# AFE.net
KiCad netlist of a schematic drawn in Altium Designer
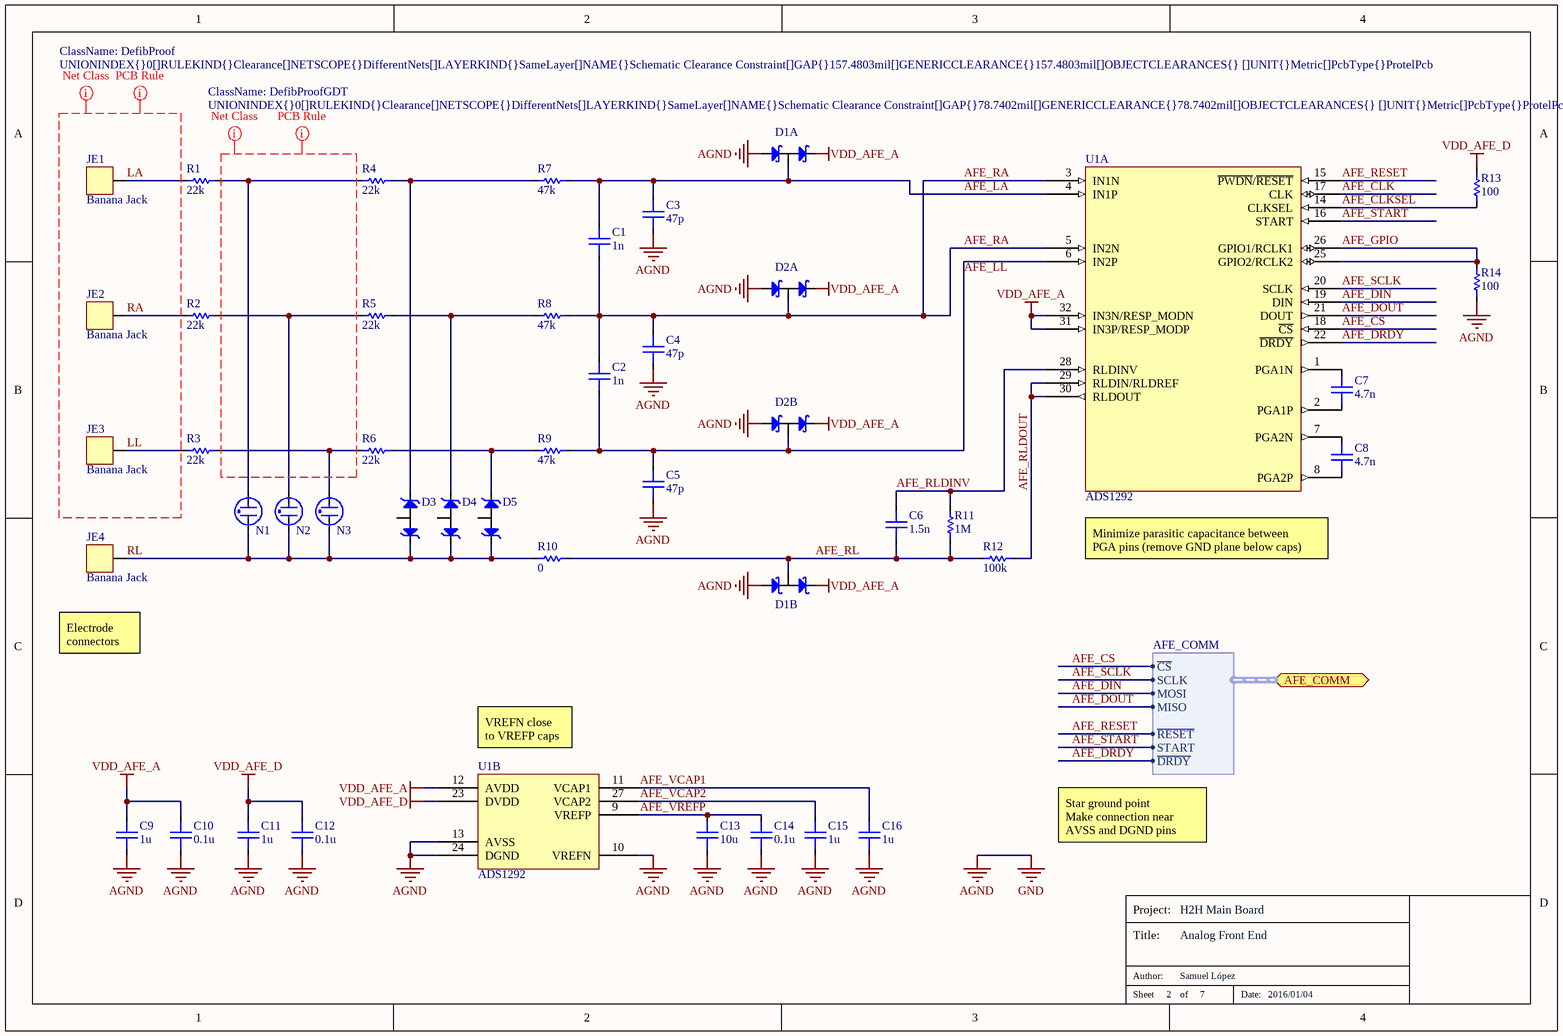
[diagram p0: AFE.SchDoc]

(export (version "E")
  (design (tool "Eeschema 10.0.6"))
  (components
    (comp (ref "C1")
      (value "1n")
      (footprint "C0603")
      (description "Capacitor")
      (libsource (lib "Misc") (part "Capacitor"))
    )
    (comp (ref "C2")
      (value "1n")
      (footprint "C0603")
      (description "Capacitor")
      (libsource (lib "Misc") (part "Capacitor"))
    )
    (comp (ref "C3")
      (value "47p")
      (footprint "C0603")
      (description "Capacitor")
      (libsource (lib "Misc") (part "Capacitor"))
    )
    (comp (ref "C4")
      (value "47p")
      (footprint "C0603")
      (description "Capacitor")
      (libsource (lib "Misc") (part "Capacitor"))
    )
    (comp (ref "C5")
      (value "47p")
      (footprint "C0603")
      (description "Capacitor")
      (libsource (lib "Misc") (part "Capacitor"))
    )
    (comp (ref "C6")
      (value "1.5n")
      (footprint "C0603")
      (description "Capacitor")
      (libsource (lib "Misc") (part "Capacitor"))
    )
    (comp (ref "C7")
      (value "4.7n")
      (footprint "C0603")
      (description "Capacitor")
      (libsource (lib "Misc") (part "Capacitor"))
    )
    (comp (ref "C8")
      (value "4.7n")
      (footprint "C0603")
      (description "Capacitor")
      (libsource (lib "Misc") (part "Capacitor"))
    )
    (comp (ref "C9")
      (value "1u")
      (footprint "C0603")
      (description "Capacitor")
      (libsource (lib "Misc") (part "Capacitor"))
    )
    (comp (ref "C10")
      (value "0.1u")
      (footprint "C0603")
      (description "Capacitor")
      (libsource (lib "Misc") (part "Capacitor"))
    )
    (comp (ref "C11")
      (value "1u")
      (footprint "C0603")
      (description "Capacitor")
      (libsource (lib "Misc") (part "Capacitor"))
    )
    (comp (ref "C12")
      (value "0.1u")
      (footprint "C0603")
      (description "Capacitor")
      (libsource (lib "Misc") (part "Capacitor"))
    )
    (comp (ref "C13")
      (value "10u")
      (footprint "C0603")
      (description "Capacitor")
      (libsource (lib "Misc") (part "Capacitor"))
    )
    (comp (ref "C14")
      (value "0.1u")
      (footprint "C0603")
      (description "Capacitor")
      (libsource (lib "Misc") (part "Capacitor"))
    )
    (comp (ref "C15")
      (value "1u")
      (footprint "C0603")
      (description "Capacitor")
      (libsource (lib "Misc") (part "Capacitor"))
    )
    (comp (ref "C16")
      (value "1u")
      (footprint "C0603")
      (description "Capacitor")
      (libsource (lib "Misc") (part "Capacitor"))
    )
    (comp (ref "D1")
      (value "BAS70DW-04")
      (footprint "BAS70DW-04")
      (description "TVS - Dual Schottky Rail-to-rail Protection")
      (libsource (lib "") (part "BAS70DW-04_1"))
    )
    (comp (ref "D2")
      (value "BAS70DW-04")
      (footprint "BAS70DW-04")
      (description "TVS - Dual Schottky Rail-to-rail Protection")
      (libsource (lib "H2H") (part "BAS70DW-04"))
    )
    (comp (ref "D3")
      (value "PESD5V0X1")
      (footprint "PESD5V0X1BT")
      (description "TVS - Bidirectional Zener Diode")
      (libsource (lib "H2H") (part "PESD5V0X1"))
    )
    (comp (ref "D4")
      (value "PESD5V0X1")
      (footprint "PESD5V0X1BT")
      (description "TVS - Bidirectional Zener Diode")
      (libsource (lib "H2H") (part "PESD5V0X1"))
    )
    (comp (ref "D5")
      (value "PESD5V0X1")
      (footprint "PESD5V0X1BT")
      (description "TVS - Bidirectional Zener Diode")
      (libsource (lib "H2H") (part "PESD5V0X1"))
    )
    (comp (ref "JE1")
      (value "Banana Jack")
      (footprint "CT3151-6")
      (description "Conn - 4mm Banana Female Jack, PCB mount, Right Angle")
      (libsource (lib "Conn") (part "CT3151SP-6"))
    )
    (comp (ref "JE2")
      (value "Banana Jack")
      (footprint "CT3151-6")
      (description "Conn - 4mm Banana Female Jack, PCB mount, Right Angle")
      (libsource (lib "Conn") (part "CT3151SP-6"))
    )
    (comp (ref "JE3")
      (value "Banana Jack")
      (footprint "CT3151-6")
      (description "Conn - 4mm Banana Female Jack, PCB mount, Right Angle")
      (libsource (lib "Conn") (part "CT3151SP-6"))
    )
    (comp (ref "JE4")
      (value "Banana Jack")
      (footprint "CT3151-6")
      (description "Conn - 4mm Banana Female Jack, PCB mount, Right Angle")
      (libsource (lib "Conn") (part "CT3151SP-6"))
    )
    (comp (ref "N1")
      (value "GDT")
      (footprint "2051-09-SM")
      (description "TVS - Gas Discharge Tube")
      (libsource (lib "H2H") (part "2051-09-SM"))
    )
    (comp (ref "N2")
      (value "GDT")
      (footprint "2051-09-SM")
      (description "TVS - Gas Discharge Tube")
      (libsource (lib "H2H") (part "2051-09-SM"))
    )
    (comp (ref "N3")
      (value "GDT")
      (footprint "2051-09-SM")
      (description "TVS - Gas Discharge Tube")
      (libsource (lib "H2H") (part "2051-09-SM"))
    )
    (comp (ref "R1")
      (value "22k")
      (footprint "R2512")
      (description "Resistor")
      (fields (field (name "POWER") "1W"))
      (libsource (lib "Misc") (part "Resistor"))
    )
    (comp (ref "R2")
      (value "22k")
      (footprint "R2512")
      (description "Resistor")
      (fields (field (name "POWER") "1W"))
      (libsource (lib "Misc") (part "Resistor"))
    )
    (comp (ref "R3")
      (value "22k")
      (footprint "R2512")
      (description "Resistor")
      (fields (field (name "POWER") "1W"))
      (libsource (lib "Misc") (part "Resistor"))
    )
    (comp (ref "R4")
      (value "22k")
      (footprint "R2512")
      (description "Resistor")
      (fields (field (name "POWER") "1W"))
      (libsource (lib "Misc") (part "Resistor"))
    )
    (comp (ref "R5")
      (value "22k")
      (footprint "R2512")
      (description "Resistor")
      (fields (field (name "POWER") "1W"))
      (libsource (lib "Misc") (part "Resistor"))
    )
    (comp (ref "R6")
      (value "22k")
      (footprint "R2512")
      (description "Resistor")
      (fields (field (name "POWER") "1W"))
      (libsource (lib "Misc") (part "Resistor"))
    )
    (comp (ref "R7")
      (value "47k")
      (footprint "R0603")
      (description "Resistor")
      (libsource (lib "Misc") (part "Resistor"))
    )
    (comp (ref "R8")
      (value "47k")
      (footprint "R0603")
      (description "Resistor")
      (libsource (lib "Misc") (part "Resistor"))
    )
    (comp (ref "R9")
      (value "47k")
      (footprint "R0603")
      (description "Resistor")
      (libsource (lib "Misc") (part "Resistor"))
    )
    (comp (ref "R10")
      (value "0")
      (footprint "R0603")
      (description "Resistor")
      (libsource (lib "Misc") (part "Resistor"))
    )
    (comp (ref "R11")
      (value "1M")
      (footprint "R0603")
      (description "Resistor")
      (libsource (lib "Misc") (part "Resistor"))
    )
    (comp (ref "R12")
      (value "100k")
      (footprint "R0603")
      (description "Resistor")
      (libsource (lib "Misc") (part "Resistor"))
    )
    (comp (ref "R13")
      (value "100")
      (footprint "R0603")
      (description "Resistor")
      (libsource (lib "Misc") (part "Resistor"))
    )
    (comp (ref "R14")
      (value "100")
      (footprint "R0603")
      (description "Resistor")
      (libsource (lib "Misc") (part "Resistor"))
    )
    (comp (ref "U1")
      (value "ADS1292")
      (footprint "ADS129x")
      (description "IC - Analog Front End - Medical")
      (libsource (lib "H2H") (part "ADS1292"))
    )
  )
  (nets
    (net (code "2") (name "/AFE_CLK") (class "Default")
      (node (ref "U1") (pin "17") (pinfunction "CLK_17") (pintype "bidirectional"))
    )
    (net (code "3") (name "/AFE_CLKSEL") (class "Default")
      (node (ref "R13") (pin "2") (pinfunction "2_2") (pintype "passive"))
      (node (ref "U1") (pin "14") (pinfunction "CLKSEL_14") (pintype "input"))
    )
    (net (code "4") (name "/AFE_CS") (class "Default")
      (node (ref "U1") (pin "18") (pinfunction "~{CS}_18") (pintype "input"))
    )
    (net (code "5") (name "/AFE_DIN") (class "Default")
      (node (ref "U1") (pin "19") (pinfunction "DIN_19") (pintype "input"))
    )
    (net (code "6") (name "/AFE_DOUT") (class "Default")
      (node (ref "U1") (pin "21") (pinfunction "DOUT_21") (pintype "output"))
    )
    (net (code "7") (name "/AFE_DRDY") (class "Default")
      (node (ref "U1") (pin "22") (pinfunction "~{DRDY}_22") (pintype "output"))
    )
    (net (code "8") (name "/AFE_GPIO") (class "Default")
      (node (ref "R14") (pin "1") (pinfunction "1_1") (pintype "passive"))
      (node (ref "U1") (pin "25") (pinfunction "GPIO2/RCLK2_25") (pintype "bidirectional"))
      (node (ref "U1") (pin "26") (pinfunction "GPIO1/RCLK1_26") (pintype "bidirectional"))
    )
    (net (code "9") (name "/AFE_LA") (class "Default")
      (node (ref "C1") (pin "2") (pinfunction "2_2") (pintype "passive"))
      (node (ref "C3") (pin "2") (pinfunction "2_2") (pintype "passive"))
      (node (ref "D1") (pin "6") (pinfunction "AK1_6") (pintype "passive"))
      (node (ref "R7") (pin "2") (pinfunction "2_2") (pintype "passive"))
      (node (ref "U1") (pin "4") (pinfunction "IN1P_4") (pintype "input"))
    )
    (net (code "10") (name "/AFE_LL") (class "Default")
      (node (ref "C2") (pin "1") (pinfunction "1_1") (pintype "passive"))
      (node (ref "C5") (pin "2") (pinfunction "2_2") (pintype "passive"))
      (node (ref "D2") (pin "3") (pinfunction "AK2_3") (pintype "passive"))
      (node (ref "R9") (pin "2") (pinfunction "2_2") (pintype "passive"))
      (node (ref "U1") (pin "6") (pinfunction "IN2P_6") (pintype "input"))
    )
    (net (code "11") (name "/AFE_RA") (class "Default")
      (node (ref "C1") (pin "1") (pinfunction "1_1") (pintype "passive"))
      (node (ref "C2") (pin "2") (pinfunction "2_2") (pintype "passive"))
      (node (ref "C4") (pin "2") (pinfunction "2_2") (pintype "passive"))
      (node (ref "D2") (pin "6") (pinfunction "AK1_6") (pintype "passive"))
      (node (ref "R8") (pin "2") (pinfunction "2_2") (pintype "passive"))
      (node (ref "U1") (pin "3") (pinfunction "IN1N_3") (pintype "input"))
      (node (ref "U1") (pin "5") (pinfunction "IN2N_5") (pintype "input"))
    )
    (net (code "12") (name "/AFE_RESET") (class "Default")
      (node (ref "U1") (pin "15") (pinfunction "~{PWDN}/~{RESET}_15") (pintype "input"))
    )
    (net (code "13") (name "/AFE_RL") (class "Default")
      (node (ref "C6") (pin "2") (pinfunction "2_2") (pintype "passive"))
      (node (ref "D1") (pin "3") (pinfunction "AK2_3") (pintype "passive"))
      (node (ref "R10") (pin "2") (pinfunction "2_2") (pintype "passive"))
      (node (ref "R11") (pin "2") (pinfunction "2_2") (pintype "passive"))
      (node (ref "R12") (pin "2") (pinfunction "2_2") (pintype "passive"))
    )
    (net (code "14") (name "/AFE_RLDINV") (class "Default")
      (node (ref "C6") (pin "1") (pinfunction "1_1") (pintype "passive"))
      (node (ref "R11") (pin "1") (pinfunction "1_1") (pintype "passive"))
      (node (ref "U1") (pin "28") (pinfunction "RLDINV_28") (pintype "input"))
    )
    (net (code "15") (name "/AFE_RLDOUT") (class "Default")
      (node (ref "R12") (pin "1") (pinfunction "1_1") (pintype "passive"))
      (node (ref "U1") (pin "29") (pinfunction "RLDIN/RLDREF_29") (pintype "input"))
      (node (ref "U1") (pin "30") (pinfunction "RLDOUT_30") (pintype "output"))
    )
    (net (code "16") (name "/AFE_SCLK") (class "Default")
      (node (ref "U1") (pin "20") (pinfunction "SCLK_20") (pintype "input"))
    )
    (net (code "17") (name "/AFE_START") (class "Default")
      (node (ref "U1") (pin "16") (pinfunction "START_16") (pintype "input"))
    )
    (net (code "18") (name "/AFE_VCAP1") (class "Default")
      (node (ref "C16") (pin "2") (pinfunction "2_2") (pintype "passive"))
      (node (ref "U1") (pin "11") (pinfunction "VCAP1_11") (pintype "passive"))
    )
    (net (code "19") (name "/AFE_VCAP2") (class "Default")
      (node (ref "C15") (pin "2") (pinfunction "2_2") (pintype "passive"))
      (node (ref "U1") (pin "27") (pinfunction "VCAP2_27") (pintype "passive"))
    )
    (net (code "20") (name "/AFE_VREFP") (class "Default")
      (node (ref "C13") (pin "2") (pinfunction "2_2") (pintype "passive"))
      (node (ref "C14") (pin "2") (pinfunction "2_2") (pintype "passive"))
      (node (ref "U1") (pin "9") (pinfunction "VREFP_9") (pintype "passive"))
    )
    (net (code "21") (name "/LA") (class "Default")
      (node (ref "JE1") (pin "1") (pinfunction "1_1") (pintype "passive"))
      (node (ref "R1") (pin "1") (pinfunction "1_1") (pintype "passive"))
    )
    (net (code "22") (name "/LL") (class "Default")
      (node (ref "JE3") (pin "1") (pinfunction "1_1") (pintype "passive"))
      (node (ref "R3") (pin "1") (pinfunction "1_1") (pintype "passive"))
    )
    (net (code "23") (name "/RA") (class "Default")
      (node (ref "JE2") (pin "1") (pinfunction "1_1") (pintype "passive"))
      (node (ref "R2") (pin "1") (pinfunction "1_1") (pintype "passive"))
    )
    (net (code "24") (name "/RL") (class "Default")
      (node (ref "D3") (pin "1") (pinfunction "K1_1") (pintype "passive"))
      (node (ref "D4") (pin "1") (pinfunction "K1_1") (pintype "passive"))
      (node (ref "D5") (pin "1") (pinfunction "K1_1") (pintype "passive"))
      (node (ref "JE4") (pin "1") (pinfunction "1_1") (pintype "passive"))
      (node (ref "N1") (pin "1") (pinfunction "1_1") (pintype "passive"))
      (node (ref "N2") (pin "1") (pinfunction "1_1") (pintype "passive"))
      (node (ref "N3") (pin "1") (pinfunction "1_1") (pintype "passive"))
      (node (ref "R10") (pin "1") (pinfunction "1_1") (pintype "passive"))
    )
    (net (code "26") (name "AGND") (class "Default")
      (node (ref "C10") (pin "1") (pinfunction "1_1") (pintype "passive"))
      (node (ref "C11") (pin "1") (pinfunction "1_1") (pintype "passive"))
      (node (ref "C12") (pin "1") (pinfunction "1_1") (pintype "passive"))
      (node (ref "C13") (pin "1") (pinfunction "1_1") (pintype "passive"))
      (node (ref "C14") (pin "1") (pinfunction "1_1") (pintype "passive"))
      (node (ref "C15") (pin "1") (pinfunction "1_1") (pintype "passive"))
      (node (ref "C16") (pin "1") (pinfunction "1_1") (pintype "passive"))
      (node (ref "C3") (pin "1") (pinfunction "1_1") (pintype "passive"))
      (node (ref "C4") (pin "1") (pinfunction "1_1") (pintype "passive"))
      (node (ref "C5") (pin "1") (pinfunction "1_1") (pintype "passive"))
      (node (ref "C9") (pin "1") (pinfunction "1_1") (pintype "passive"))
      (node (ref "D1") (pin "1") (pinfunction "A1_1") (pintype "passive"))
      (node (ref "D1") (pin "4") (pinfunction "A2_4") (pintype "passive"))
      (node (ref "D2") (pin "1") (pinfunction "A1_1") (pintype "passive"))
      (node (ref "D2") (pin "4") (pinfunction "A2_4") (pintype "passive"))
      (node (ref "R14") (pin "2") (pinfunction "2_2") (pintype "passive"))
      (node (ref "U1") (pin "10") (pinfunction "VREFN_10") (pintype "passive"))
      (node (ref "U1") (pin "13") (pinfunction "AVSS_13") (pintype "power_in"))
      (node (ref "U1") (pin "24") (pinfunction "DGND_24") (pintype "power_in"))
    )
    (net (code "27") (name "Net-(D3-K2)") (class "Default")
      (node (ref "D3") (pin "2") (pinfunction "K2_2") (pintype "passive"))
      (node (ref "R4") (pin "2") (pinfunction "2_2") (pintype "passive"))
      (node (ref "R7") (pin "1") (pinfunction "1_1") (pintype "passive"))
    )
    (net (code "28") (name "Net-(D4-K2)") (class "Default")
      (node (ref "D4") (pin "2") (pinfunction "K2_2") (pintype "passive"))
      (node (ref "R5") (pin "2") (pinfunction "2_2") (pintype "passive"))
      (node (ref "R8") (pin "1") (pinfunction "1_1") (pintype "passive"))
    )
    (net (code "29") (name "Net-(D5-K2)") (class "Default")
      (node (ref "D5") (pin "2") (pinfunction "K2_2") (pintype "passive"))
      (node (ref "R6") (pin "2") (pinfunction "2_2") (pintype "passive"))
      (node (ref "R9") (pin "1") (pinfunction "1_1") (pintype "passive"))
    )
    (net (code "30") (name "Net-(N1-Pad2)") (class "Default")
      (node (ref "N1") (pin "2") (pinfunction "2_2") (pintype "passive"))
      (node (ref "R1") (pin "2") (pinfunction "2_2") (pintype "passive"))
      (node (ref "R4") (pin "1") (pinfunction "1_1") (pintype "passive"))
    )
    (net (code "31") (name "Net-(N2-Pad2)") (class "Default")
      (node (ref "N2") (pin "2") (pinfunction "2_2") (pintype "passive"))
      (node (ref "R2") (pin "2") (pinfunction "2_2") (pintype "passive"))
      (node (ref "R5") (pin "1") (pinfunction "1_1") (pintype "passive"))
    )
    (net (code "32") (name "Net-(N3-Pad2)") (class "Default")
      (node (ref "N3") (pin "2") (pinfunction "2_2") (pintype "passive"))
      (node (ref "R3") (pin "2") (pinfunction "2_2") (pintype "passive"))
      (node (ref "R6") (pin "1") (pinfunction "1_1") (pintype "passive"))
    )
    (net (code "33") (name "Net-(U1A-PGA1N)") (class "Default")
      (node (ref "C7") (pin "2") (pinfunction "2_2") (pintype "passive"))
      (node (ref "U1") (pin "1") (pinfunction "PGA1N_1") (pintype "output"))
    )
    (net (code "34") (name "Net-(U1A-PGA1P)") (class "Default")
      (node (ref "C7") (pin "1") (pinfunction "1_1") (pintype "passive"))
      (node (ref "U1") (pin "2") (pinfunction "PGA1P_2") (pintype "output"))
    )
    (net (code "35") (name "Net-(U1A-PGA2N)") (class "Default")
      (node (ref "C8") (pin "2") (pinfunction "2_2") (pintype "passive"))
      (node (ref "U1") (pin "7") (pinfunction "PGA2N_7") (pintype "output"))
    )
    (net (code "36") (name "Net-(U1A-PGA2P)") (class "Default")
      (node (ref "C8") (pin "1") (pinfunction "1_1") (pintype "passive"))
      (node (ref "U1") (pin "8") (pinfunction "PGA2P_8") (pintype "output"))
    )
    (net (code "37") (name "VDD_AFE_A") (class "Default")
      (node (ref "C10") (pin "2") (pinfunction "2_2") (pintype "passive"))
      (node (ref "C9") (pin "2") (pinfunction "2_2") (pintype "passive"))
      (node (ref "D1") (pin "2") (pinfunction "K1_2") (pintype "passive"))
      (node (ref "D1") (pin "5") (pinfunction "K2_5") (pintype "passive"))
      (node (ref "D2") (pin "2") (pinfunction "K1_2") (pintype "passive"))
      (node (ref "D2") (pin "5") (pinfunction "K2_5") (pintype "passive"))
      (node (ref "U1") (pin "12") (pinfunction "AVDD_12") (pintype "power_in"))
      (node (ref "U1") (pin "31") (pinfunction "IN3P/RESP_MODP_31") (pintype "input"))
      (node (ref "U1") (pin "32") (pinfunction "IN3N/RESP_MODN_32") (pintype "input"))
    )
    (net (code "38") (name "VDD_AFE_D") (class "Default")
      (node (ref "C11") (pin "2") (pinfunction "2_2") (pintype "passive"))
      (node (ref "C12") (pin "2") (pinfunction "2_2") (pintype "passive"))
      (node (ref "R13") (pin "1") (pinfunction "1_1") (pintype "passive"))
      (node (ref "U1") (pin "23") (pinfunction "DVDD_23") (pintype "power_in"))
    )
    (net (code "39") (name "unconnected-(D3-A-Pad3)") (class "Default")
      (node (ref "D3") (pin "3") (pinfunction "A_3") (pintype "passive"))
    )
    (net (code "40") (name "unconnected-(D4-A-Pad3)") (class "Default")
      (node (ref "D4") (pin "3") (pinfunction "A_3") (pintype "passive"))
    )
    (net (code "41") (name "unconnected-(D5-A-Pad3)") (class "Default")
      (node (ref "D5") (pin "3") (pinfunction "A_3") (pintype "passive"))
    )
  )
)
